# lajta-hfcs.net
KiCad netlist of a schematic drawn in EAGLE
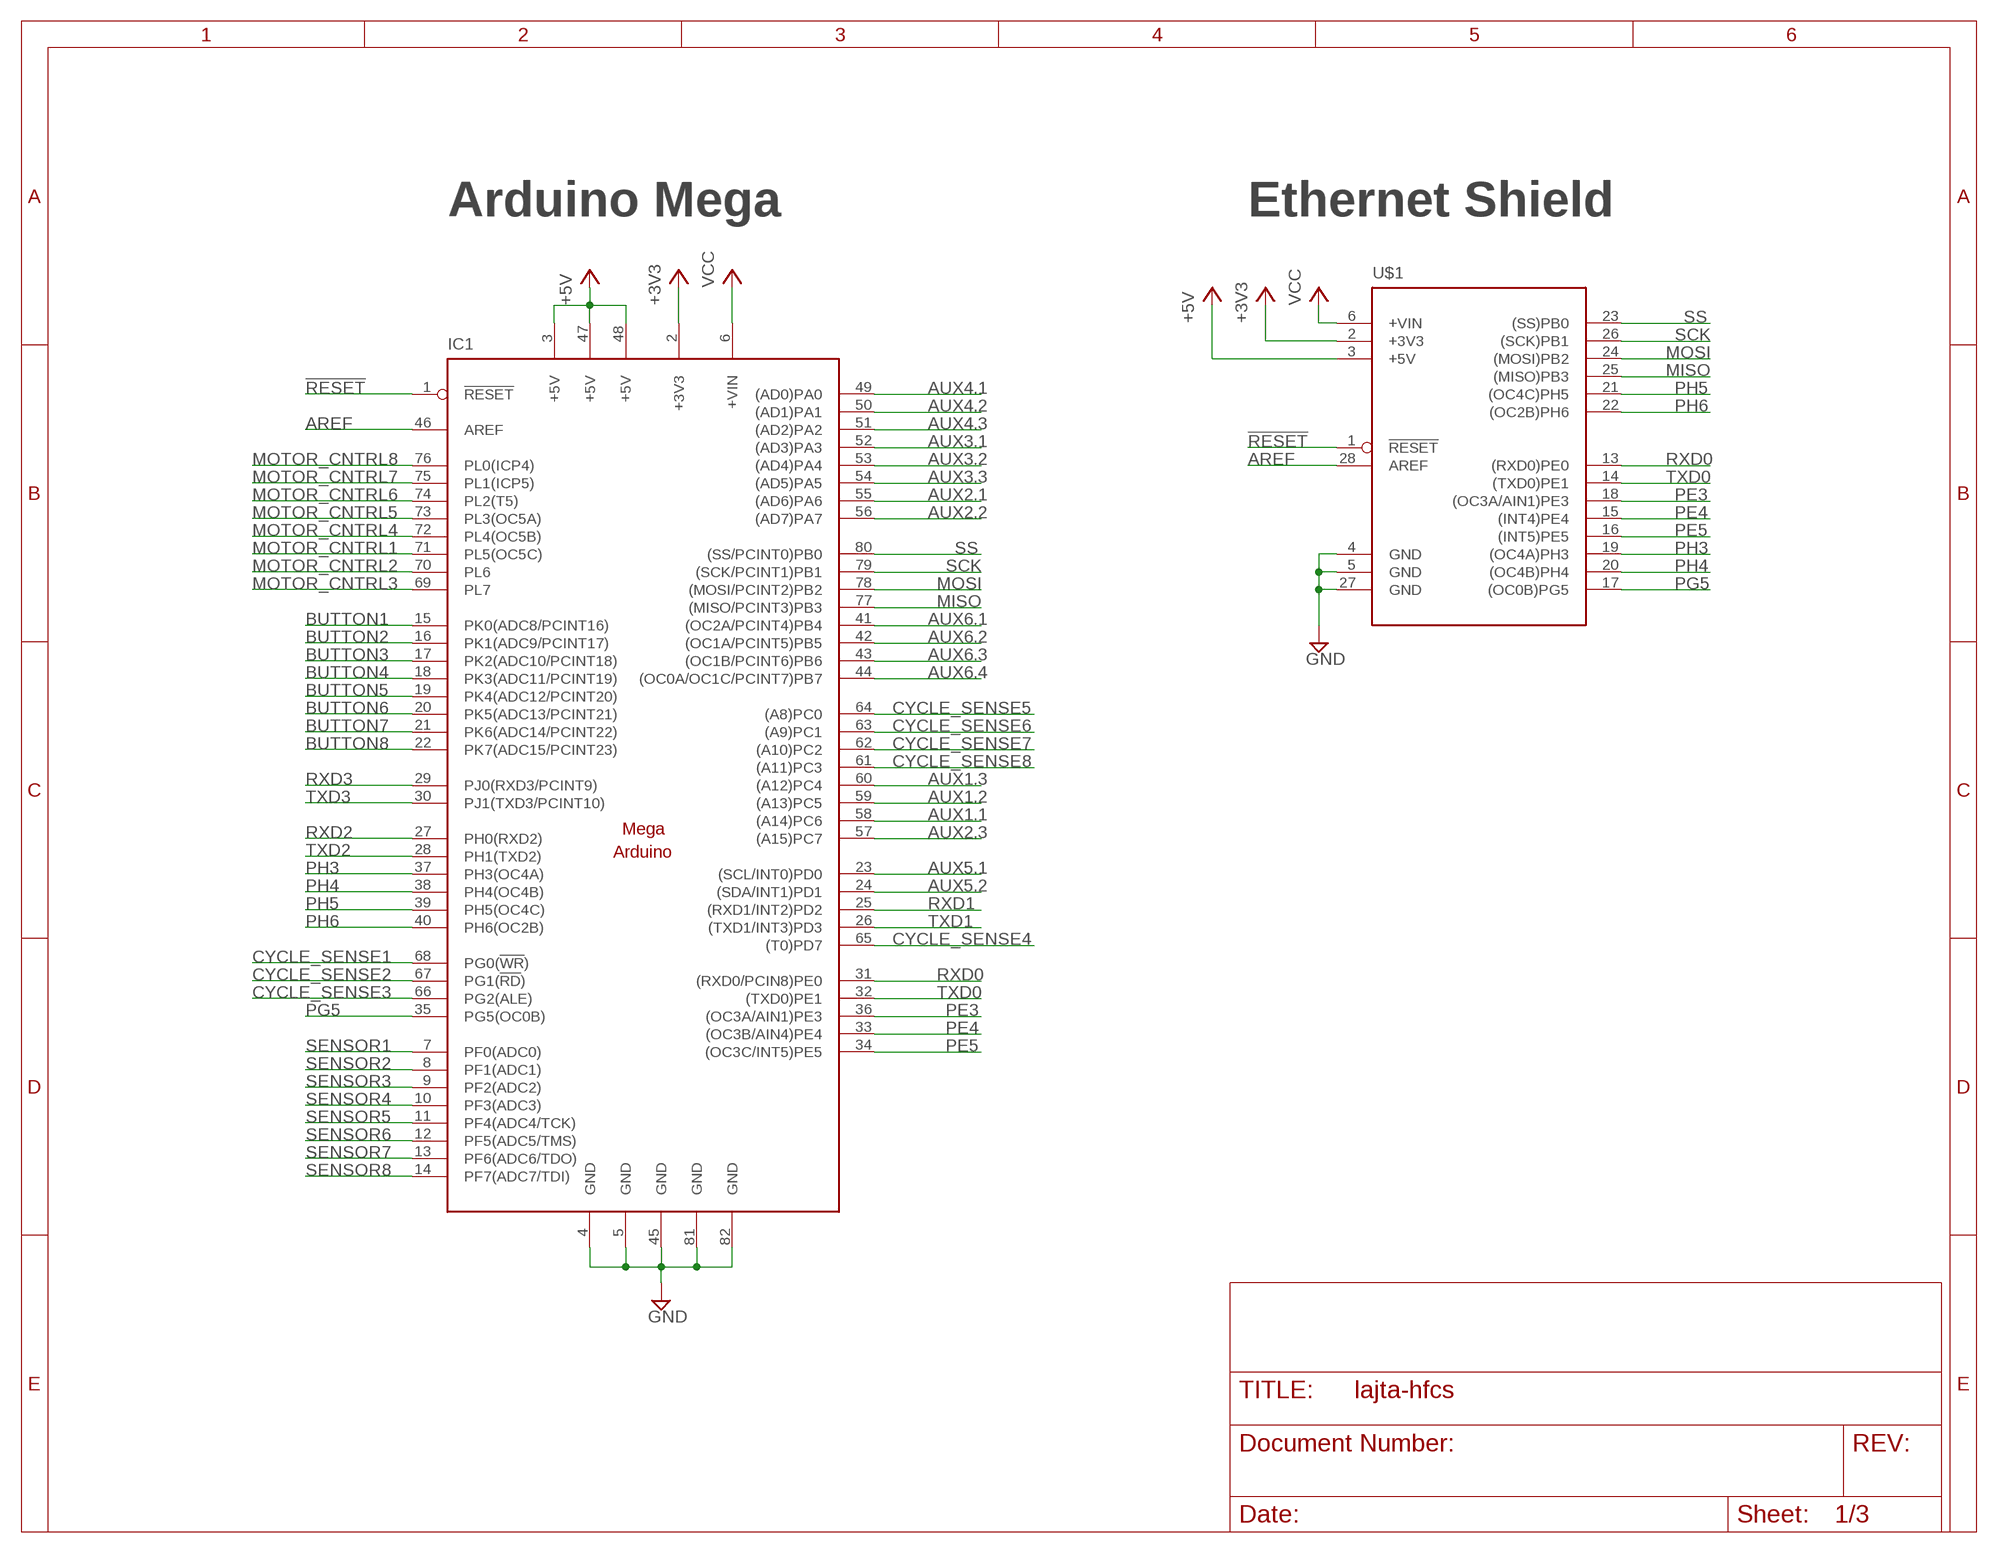
[diagram p0: schematic, sheet 1]
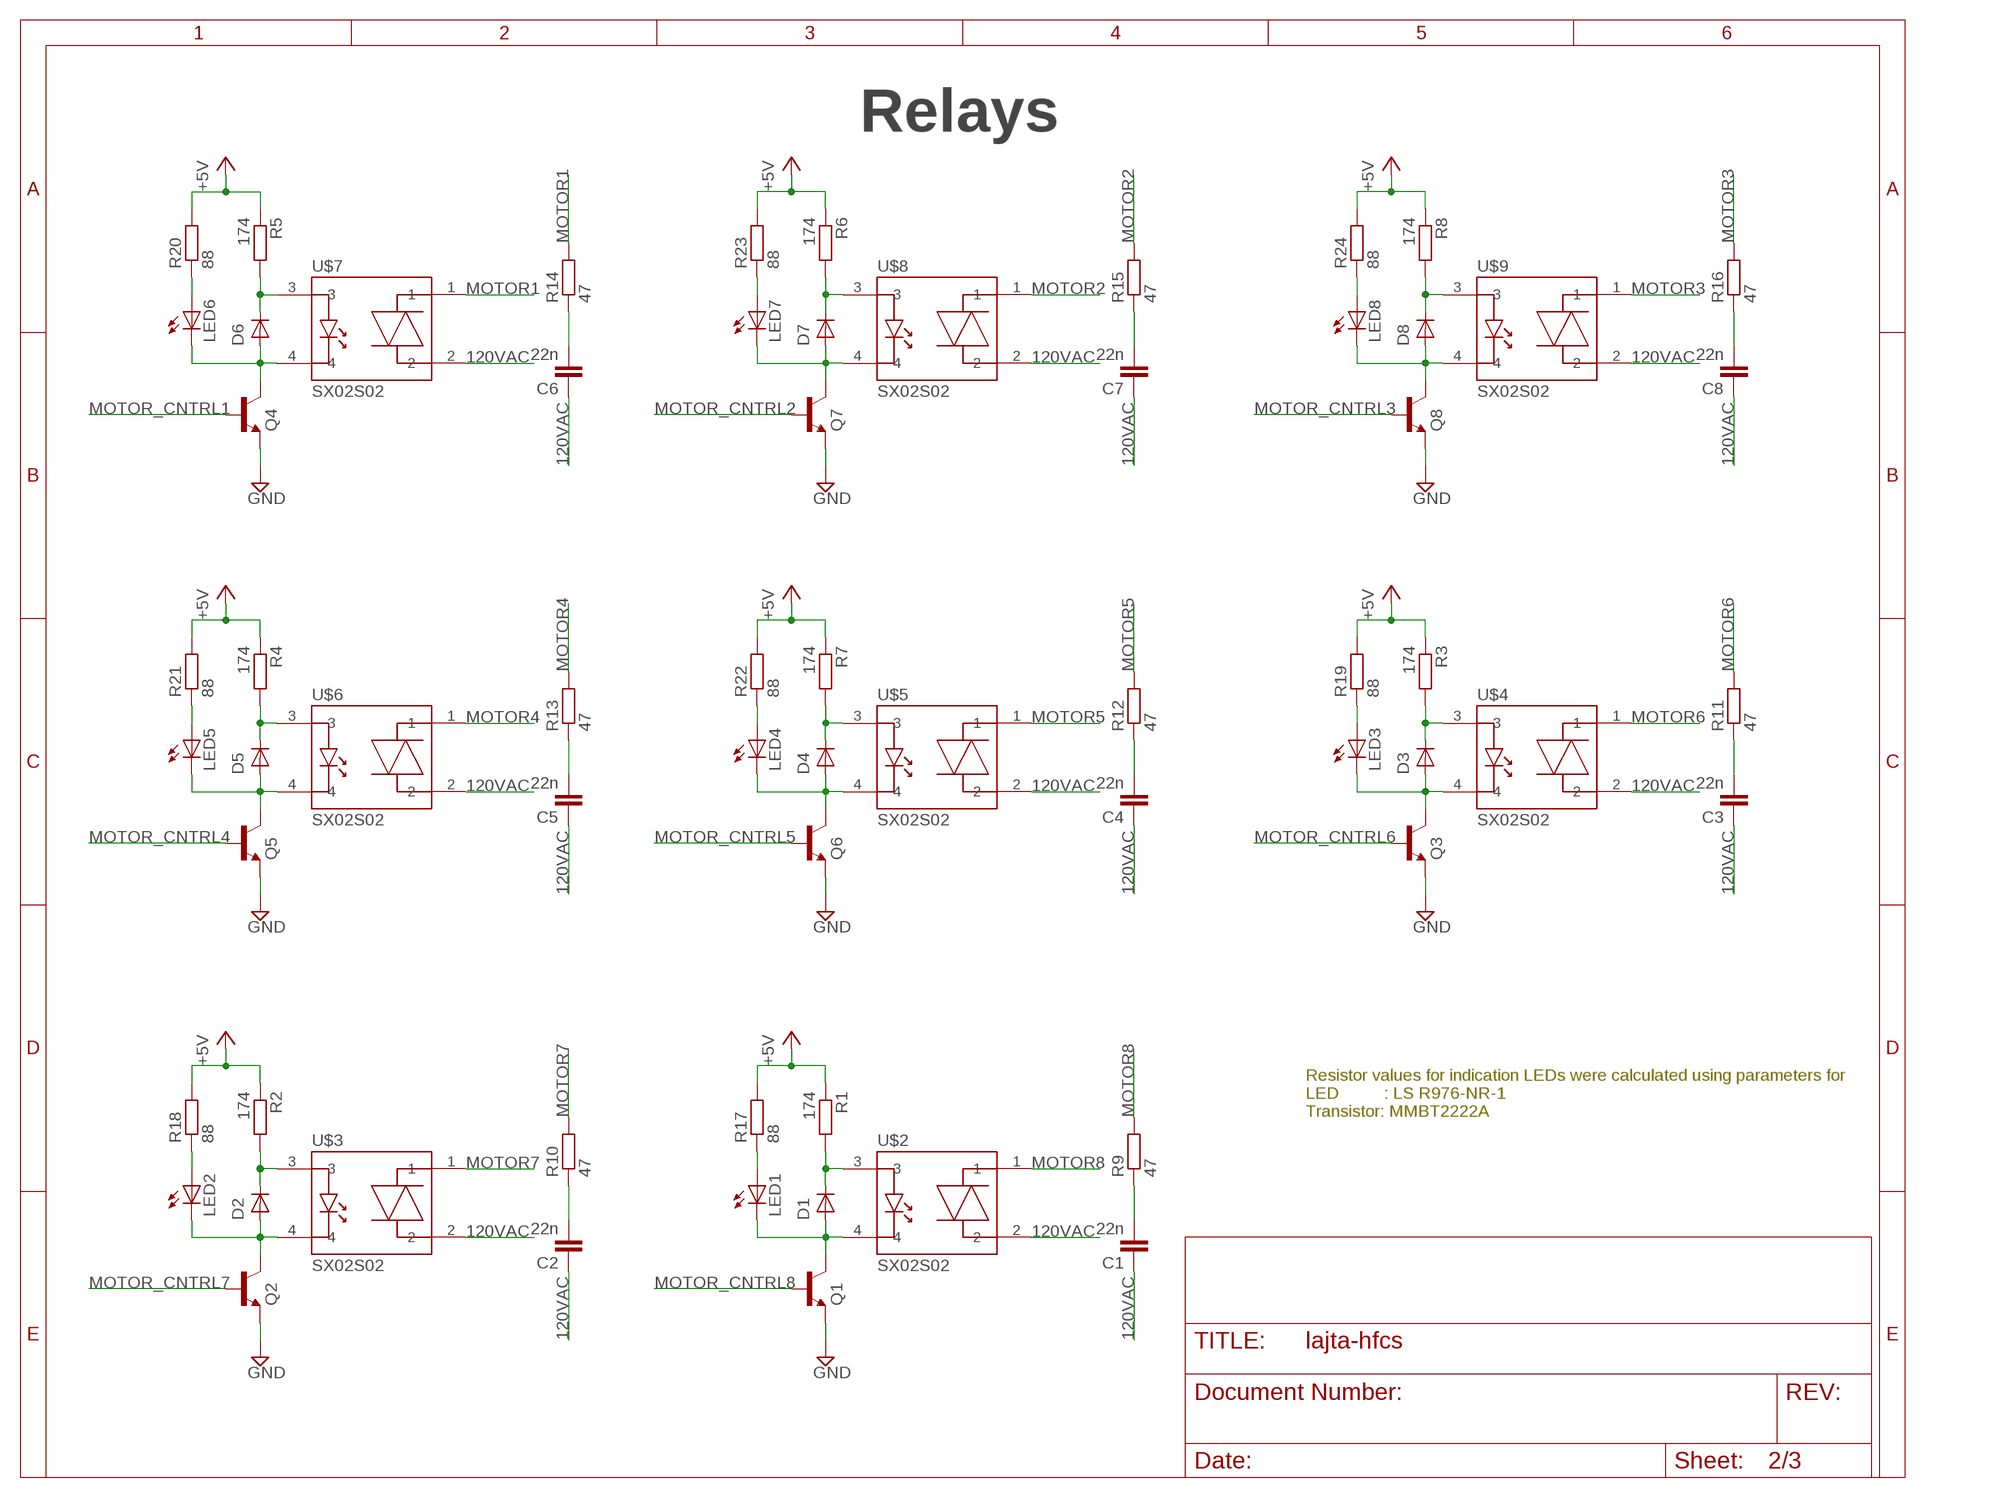
[diagram p1: schematic, sheet 2]
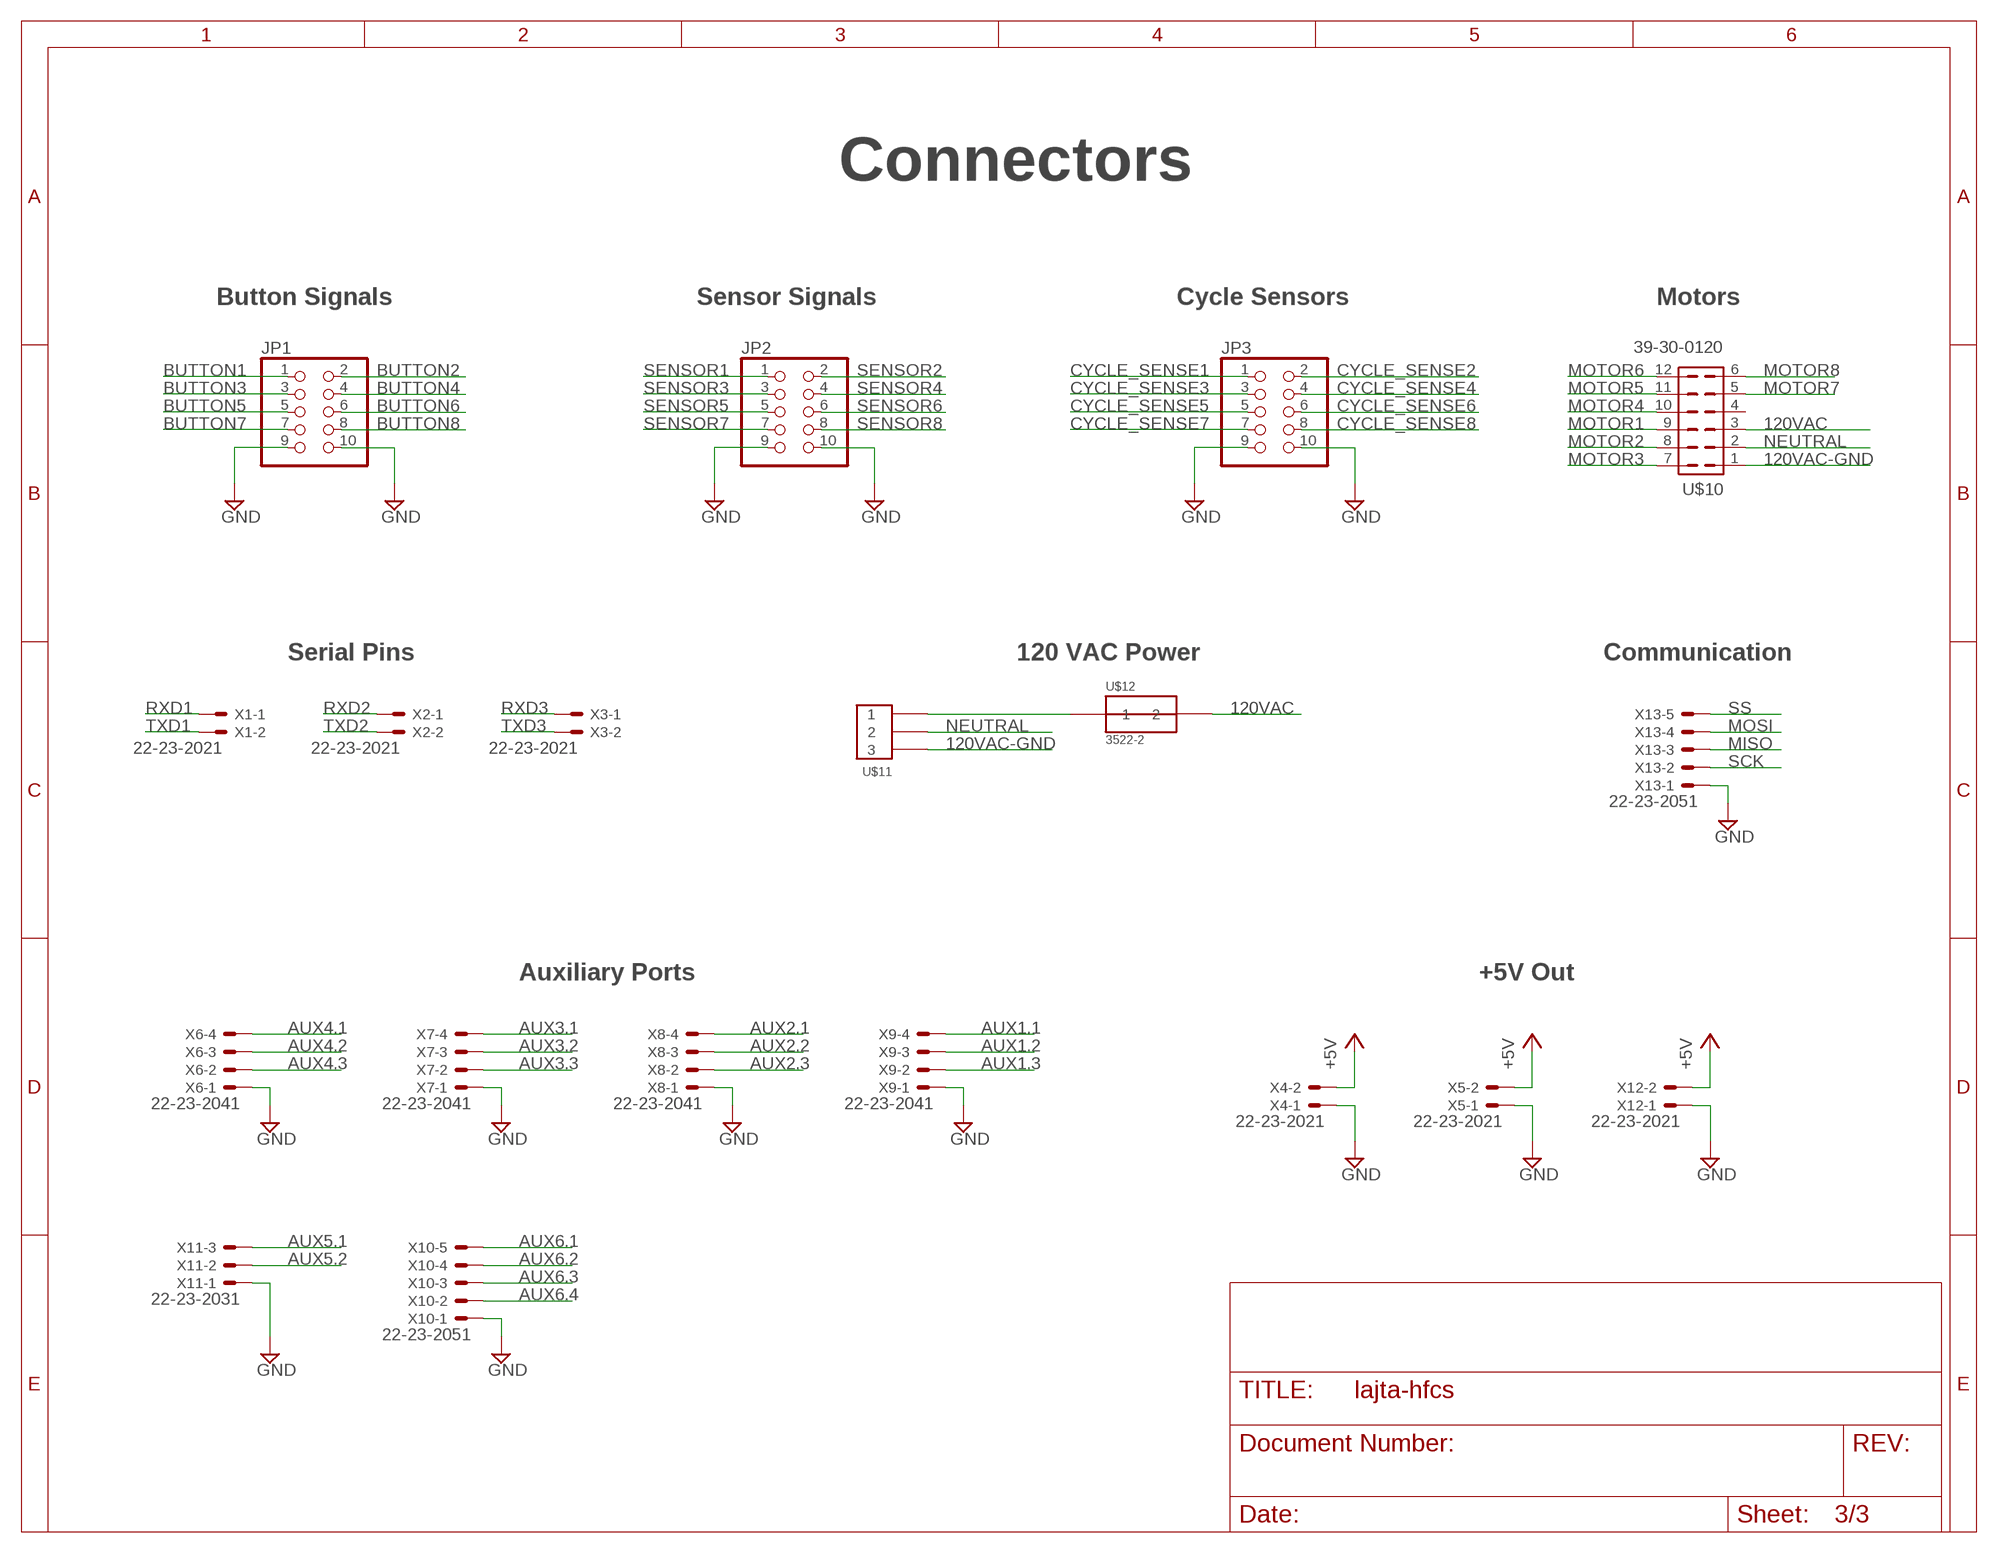
[diagram p2: schematic, sheet 3]

(export (version "E")
  (design (tool "Eeschema 10.0.6"))
  (components
    (comp (ref "JP1")
      (value "PINHD-2X05_2.00")
      (footprint "eagle-import:2X05M")
      (libsource (lib "eagle-import") (part "PINHD-2X05_2.00"))
    )
    (comp (ref "JP2")
      (value "PINHD-2X05_2.00")
      (footprint "eagle-import:2X05M")
      (libsource (lib "eagle-import") (part "PINHD-2X05_2.00"))
    )
    (comp (ref "JP3")
      (value "PINHD-2X05_2.00")
      (footprint "eagle-import:2X05M")
      (libsource (lib "eagle-import") (part "PINHD-2X05_2.00"))
    )
    (comp (ref "U$10")
      (value "39-30-0120")
      (footprint "eagle-import:MINIFIT5569-2-6")
      (libsource (lib "eagle-import") (part "39-30-0120"))
    )
    (comp (ref "U$11")
      (value "39-30-3035")
      (footprint "eagle-import:39-30-3035")
      (libsource (lib "eagle-import") (part "39-30-3035"))
    )
    (comp (ref "U$12")
      (value "3522-2")
      (footprint "eagle-import:ATC")
      (libsource (lib "eagle-import") (part "3522-2"))
    )
    (comp (ref "X1")
      (value "22-23-2021")
      (footprint "eagle-import:22-23-2021")
      (fields (field (name "MF") "MOLEX"))
      (libsource (lib "eagle-import") (part "22-23-2021"))
    )
    (comp (ref "X2")
      (value "22-23-2021")
      (footprint "eagle-import:22-23-2021")
      (fields (field (name "MF") "MOLEX"))
      (libsource (lib "eagle-import") (part "22-23-2021"))
    )
    (comp (ref "X3")
      (value "22-23-2021")
      (footprint "eagle-import:22-23-2021")
      (fields (field (name "MF") "MOLEX"))
      (libsource (lib "eagle-import") (part "22-23-2021"))
    )
    (comp (ref "X4")
      (value "22-23-2021")
      (footprint "eagle-import:22-23-2021")
      (fields (field (name "MF") "MOLEX"))
      (libsource (lib "eagle-import") (part "22-23-2021"))
    )
    (comp (ref "X5")
      (value "22-23-2021")
      (footprint "eagle-import:22-23-2021")
      (fields (field (name "MF") "MOLEX"))
      (libsource (lib "eagle-import") (part "22-23-2021"))
    )
    (comp (ref "X6")
      (value "22-23-2041")
      (footprint "eagle-import:22-23-2041")
      (fields (field (name "MF") "MOLEX"))
      (libsource (lib "eagle-import") (part "22-23-2041"))
    )
    (comp (ref "X7")
      (value "22-23-2041")
      (footprint "eagle-import:22-23-2041")
      (fields (field (name "MF") "MOLEX"))
      (libsource (lib "eagle-import") (part "22-23-2041"))
    )
    (comp (ref "X8")
      (value "22-23-2041")
      (footprint "eagle-import:22-23-2041")
      (fields (field (name "MF") "MOLEX"))
      (libsource (lib "eagle-import") (part "22-23-2041"))
    )
    (comp (ref "X9")
      (value "22-23-2041")
      (footprint "eagle-import:22-23-2041")
      (fields (field (name "MF") "MOLEX"))
      (libsource (lib "eagle-import") (part "22-23-2041"))
    )
    (comp (ref "X10")
      (value "22-23-2051")
      (footprint "eagle-import:22-23-2051")
      (fields (field (name "MF") "MOLEX"))
      (libsource (lib "eagle-import") (part "22-23-2051"))
    )
    (comp (ref "X11")
      (value "22-23-2031")
      (footprint "eagle-import:22-23-2031")
      (fields (field (name "MF") "MOLEX"))
      (libsource (lib "eagle-import") (part "22-23-2031"))
    )
    (comp (ref "X12")
      (value "22-23-2021")
      (footprint "eagle-import:22-23-2021")
      (fields (field (name "MF") "MOLEX"))
      (libsource (lib "eagle-import") (part "22-23-2021"))
    )
    (comp (ref "X13")
      (value "22-23-2051")
      (footprint "eagle-import:22-23-2051")
      (fields (field (name "MF") "MOLEX"))
      (libsource (lib "eagle-import") (part "22-23-2051"))
    )
    (comp (ref "IC1")
      (value "MEGAARDUINO_1")
      (footprint "eagle-import:MEGA_ARDUINO")
      (libsource (lib "eagle-import") (part "MEGAARDUINO_1"))
    )
    (comp (ref "U$1")
      (value "MEGAARDUINO_ETHERNET_SHIELD")
      (footprint "eagle-import:ETHERNET_SHIELD")
      (libsource (lib "eagle-import") (part "MEGAARDUINO_ETHERNET_SHIELD"))
    )
    (comp (ref "C1")
      (value "22n")
      (footprint "eagle-import:C1812")
      (libsource (lib "eagle-import") (part "C-EUC1812"))
    )
    (comp (ref "C2")
      (value "22n")
      (footprint "eagle-import:C1812")
      (libsource (lib "eagle-import") (part "C-EUC1812"))
    )
    (comp (ref "C3")
      (value "22n")
      (footprint "eagle-import:C1812")
      (libsource (lib "eagle-import") (part "C-EUC1812"))
    )
    (comp (ref "C4")
      (value "22n")
      (footprint "eagle-import:C1812")
      (libsource (lib "eagle-import") (part "C-EUC1812"))
    )
    (comp (ref "C5")
      (value "22n")
      (footprint "eagle-import:C1812")
      (libsource (lib "eagle-import") (part "C-EUC1812"))
    )
    (comp (ref "C6")
      (value "22n")
      (footprint "eagle-import:C1812")
      (libsource (lib "eagle-import") (part "C-EUC1812"))
    )
    (comp (ref "C7")
      (value "22n")
      (footprint "eagle-import:C1812")
      (libsource (lib "eagle-import") (part "C-EUC1812"))
    )
    (comp (ref "C8")
      (value "22n")
      (footprint "eagle-import:C1812")
      (libsource (lib "eagle-import") (part "C-EUC1812"))
    )
    (comp (ref "D1")
      (value "1N4448W")
      (footprint "eagle-import:SOD123")
      (libsource (lib "eagle-import") (part "1N4448W"))
    )
    (comp (ref "D2")
      (value "1N4448W")
      (footprint "eagle-import:SOD123")
      (libsource (lib "eagle-import") (part "1N4448W"))
    )
    (comp (ref "D3")
      (value "1N4448W")
      (footprint "eagle-import:SOD123")
      (libsource (lib "eagle-import") (part "1N4448W"))
    )
    (comp (ref "D4")
      (value "1N4448W")
      (footprint "eagle-import:SOD123")
      (libsource (lib "eagle-import") (part "1N4448W"))
    )
    (comp (ref "D5")
      (value "1N4448W")
      (footprint "eagle-import:SOD123")
      (libsource (lib "eagle-import") (part "1N4448W"))
    )
    (comp (ref "D6")
      (value "1N4448W")
      (footprint "eagle-import:SOD123")
      (libsource (lib "eagle-import") (part "1N4448W"))
    )
    (comp (ref "D7")
      (value "1N4448W")
      (footprint "eagle-import:SOD123")
      (libsource (lib "eagle-import") (part "1N4448W"))
    )
    (comp (ref "D8")
      (value "1N4448W")
      (footprint "eagle-import:SOD123")
      (libsource (lib "eagle-import") (part "1N4448W"))
    )
    (comp (ref "LED1")
      (value "LEDCHIPLED_0805")
      (footprint "eagle-import:CHIPLED_0805")
      (libsource (lib "eagle-import") (part "LEDCHIPLED_0805"))
    )
    (comp (ref "LED2")
      (value "LEDCHIPLED_0805")
      (footprint "eagle-import:CHIPLED_0805")
      (libsource (lib "eagle-import") (part "LEDCHIPLED_0805"))
    )
    (comp (ref "LED3")
      (value "LEDCHIPLED_0805")
      (footprint "eagle-import:CHIPLED_0805")
      (libsource (lib "eagle-import") (part "LEDCHIPLED_0805"))
    )
    (comp (ref "LED4")
      (value "LEDCHIPLED_0805")
      (footprint "eagle-import:CHIPLED_0805")
      (libsource (lib "eagle-import") (part "LEDCHIPLED_0805"))
    )
    (comp (ref "LED5")
      (value "LEDCHIPLED_0805")
      (footprint "eagle-import:CHIPLED_0805")
      (libsource (lib "eagle-import") (part "LEDCHIPLED_0805"))
    )
    (comp (ref "LED6")
      (value "LEDCHIPLED_0805")
      (footprint "eagle-import:CHIPLED_0805")
      (libsource (lib "eagle-import") (part "LEDCHIPLED_0805"))
    )
    (comp (ref "LED7")
      (value "LEDCHIPLED_0805")
      (footprint "eagle-import:CHIPLED_0805")
      (libsource (lib "eagle-import") (part "LEDCHIPLED_0805"))
    )
    (comp (ref "LED8")
      (value "LEDCHIPLED_0805")
      (footprint "eagle-import:CHIPLED_0805")
      (libsource (lib "eagle-import") (part "LEDCHIPLED_0805"))
    )
    (comp (ref "Q1")
      (value "MMBT2222A")
      (footprint "eagle-import:SOT23")
      (libsource (lib "eagle-import") (part "MMBT2222A"))
    )
    (comp (ref "Q2")
      (value "MMBT2222A")
      (footprint "eagle-import:SOT23")
      (libsource (lib "eagle-import") (part "MMBT2222A"))
    )
    (comp (ref "Q3")
      (value "MMBT2222A")
      (footprint "eagle-import:SOT23")
      (libsource (lib "eagle-import") (part "MMBT2222A"))
    )
    (comp (ref "Q4")
      (value "MMBT2222A")
      (footprint "eagle-import:SOT23")
      (libsource (lib "eagle-import") (part "MMBT2222A"))
    )
    (comp (ref "Q5")
      (value "MMBT2222A")
      (footprint "eagle-import:SOT23")
      (libsource (lib "eagle-import") (part "MMBT2222A"))
    )
    (comp (ref "Q6")
      (value "MMBT2222A")
      (footprint "eagle-import:SOT23")
      (libsource (lib "eagle-import") (part "MMBT2222A"))
    )
    (comp (ref "Q7")
      (value "MMBT2222A")
      (footprint "eagle-import:SOT23")
      (libsource (lib "eagle-import") (part "MMBT2222A"))
    )
    (comp (ref "Q8")
      (value "MMBT2222A")
      (footprint "eagle-import:SOT23")
      (libsource (lib "eagle-import") (part "MMBT2222A"))
    )
    (comp (ref "R1")
      (value "174")
      (footprint "eagle-import:R0805")
      (libsource (lib "eagle-import") (part "R-EU_R0805"))
    )
    (comp (ref "R2")
      (value "174")
      (footprint "eagle-import:R0805")
      (libsource (lib "eagle-import") (part "R-EU_R0805"))
    )
    (comp (ref "R3")
      (value "174")
      (footprint "eagle-import:R0805")
      (libsource (lib "eagle-import") (part "R-EU_R0805"))
    )
    (comp (ref "R4")
      (value "174")
      (footprint "eagle-import:R0805")
      (libsource (lib "eagle-import") (part "R-EU_R0805"))
    )
    (comp (ref "R5")
      (value "174")
      (footprint "eagle-import:R0805")
      (libsource (lib "eagle-import") (part "R-EU_R0805"))
    )
    (comp (ref "R6")
      (value "174")
      (footprint "eagle-import:R0805")
      (libsource (lib "eagle-import") (part "R-EU_R0805"))
    )
    (comp (ref "R7")
      (value "174")
      (footprint "eagle-import:R0805")
      (libsource (lib "eagle-import") (part "R-EU_R0805"))
    )
    (comp (ref "R8")
      (value "174")
      (footprint "eagle-import:R0805")
      (libsource (lib "eagle-import") (part "R-EU_R0805"))
    )
    (comp (ref "R9")
      (value "47")
      (footprint "eagle-import:R0805")
      (libsource (lib "eagle-import") (part "R-EU_R0805"))
    )
    (comp (ref "R10")
      (value "47")
      (footprint "eagle-import:R0805")
      (libsource (lib "eagle-import") (part "R-EU_R0805"))
    )
    (comp (ref "R11")
      (value "47")
      (footprint "eagle-import:R0805")
      (libsource (lib "eagle-import") (part "R-EU_R0805"))
    )
    (comp (ref "R12")
      (value "47")
      (footprint "eagle-import:R0805")
      (libsource (lib "eagle-import") (part "R-EU_R0805"))
    )
    (comp (ref "R13")
      (value "47")
      (footprint "eagle-import:R0805")
      (libsource (lib "eagle-import") (part "R-EU_R0805"))
    )
    (comp (ref "R14")
      (value "47")
      (footprint "eagle-import:R0805")
      (libsource (lib "eagle-import") (part "R-EU_R0805"))
    )
    (comp (ref "R15")
      (value "47")
      (footprint "eagle-import:R0805")
      (libsource (lib "eagle-import") (part "R-EU_R0805"))
    )
    (comp (ref "R16")
      (value "47")
      (footprint "eagle-import:R0805")
      (libsource (lib "eagle-import") (part "R-EU_R0805"))
    )
    (comp (ref "R17")
      (value "88")
      (footprint "eagle-import:R0805")
      (libsource (lib "eagle-import") (part "R-EU_R0805"))
    )
    (comp (ref "R18")
      (value "88")
      (footprint "eagle-import:R0805")
      (libsource (lib "eagle-import") (part "R-EU_R0805"))
    )
    (comp (ref "R19")
      (value "88")
      (footprint "eagle-import:R0805")
      (libsource (lib "eagle-import") (part "R-EU_R0805"))
    )
    (comp (ref "R20")
      (value "88")
      (footprint "eagle-import:R0805")
      (libsource (lib "eagle-import") (part "R-EU_R0805"))
    )
    (comp (ref "R21")
      (value "88")
      (footprint "eagle-import:R0805")
      (libsource (lib "eagle-import") (part "R-EU_R0805"))
    )
    (comp (ref "R22")
      (value "88")
      (footprint "eagle-import:R0805")
      (libsource (lib "eagle-import") (part "R-EU_R0805"))
    )
    (comp (ref "R23")
      (value "88")
      (footprint "eagle-import:R0805")
      (libsource (lib "eagle-import") (part "R-EU_R0805"))
    )
    (comp (ref "R24")
      (value "88")
      (footprint "eagle-import:R0805")
      (libsource (lib "eagle-import") (part "R-EU_R0805"))
    )
    (comp (ref "U$2")
      (value "SX02S02")
      (footprint "eagle-import:SIP-4")
      (libsource (lib "eagle-import") (part "SX02S02"))
    )
    (comp (ref "U$3")
      (value "SX02S02")
      (footprint "eagle-import:SIP-4")
      (libsource (lib "eagle-import") (part "SX02S02"))
    )
    (comp (ref "U$4")
      (value "SX02S02")
      (footprint "eagle-import:SIP-4")
      (libsource (lib "eagle-import") (part "SX02S02"))
    )
    (comp (ref "U$5")
      (value "SX02S02")
      (footprint "eagle-import:SIP-4")
      (libsource (lib "eagle-import") (part "SX02S02"))
    )
    (comp (ref "U$6")
      (value "SX02S02")
      (footprint "eagle-import:SIP-4")
      (libsource (lib "eagle-import") (part "SX02S02"))
    )
    (comp (ref "U$7")
      (value "SX02S02")
      (footprint "eagle-import:SIP-4")
      (libsource (lib "eagle-import") (part "SX02S02"))
    )
    (comp (ref "U$8")
      (value "SX02S02")
      (footprint "eagle-import:SIP-4")
      (libsource (lib "eagle-import") (part "SX02S02"))
    )
    (comp (ref "U$9")
      (value "SX02S02")
      (footprint "eagle-import:SIP-4")
      (libsource (lib "eagle-import") (part "SX02S02"))
    )
  )
  (nets
    (net (code "1") (name "+3V3") (class "Default")
      (node (ref "IC1") (pin "2") (pinfunction "+3V3_2") (pintype "power_in"))
      (node (ref "U$1") (pin "2") (pinfunction "+3V3_2") (pintype "power_in"))
    )
    (net (code "2") (name "+5V") (class "Default")
      (node (ref "IC1") (pin "3") (pinfunction "+5V_3") (pintype "power_in"))
      (node (ref "IC1") (pin "47") (pinfunction "+5V_47") (pintype "power_in"))
      (node (ref "IC1") (pin "48") (pinfunction "+5V_48") (pintype "power_in"))
      (node (ref "R1") (pin "1") (pinfunction "1_1") (pintype "passive"))
      (node (ref "R17") (pin "2") (pinfunction "2_2") (pintype "passive"))
      (node (ref "R18") (pin "2") (pinfunction "2_2") (pintype "passive"))
      (node (ref "R19") (pin "2") (pinfunction "2_2") (pintype "passive"))
      (node (ref "R2") (pin "1") (pinfunction "1_1") (pintype "passive"))
      (node (ref "R20") (pin "2") (pinfunction "2_2") (pintype "passive"))
      (node (ref "R21") (pin "2") (pinfunction "2_2") (pintype "passive"))
      (node (ref "R22") (pin "2") (pinfunction "2_2") (pintype "passive"))
      (node (ref "R23") (pin "2") (pinfunction "2_2") (pintype "passive"))
      (node (ref "R24") (pin "2") (pinfunction "2_2") (pintype "passive"))
      (node (ref "R3") (pin "1") (pinfunction "1_1") (pintype "passive"))
      (node (ref "R4") (pin "1") (pinfunction "1_1") (pintype "passive"))
      (node (ref "R5") (pin "1") (pinfunction "1_1") (pintype "passive"))
      (node (ref "R6") (pin "1") (pinfunction "1_1") (pintype "passive"))
      (node (ref "R7") (pin "1") (pinfunction "1_1") (pintype "passive"))
      (node (ref "R8") (pin "1") (pinfunction "1_1") (pintype "passive"))
      (node (ref "U$1") (pin "3") (pinfunction "+5V_3") (pintype "power_in"))
      (node (ref "X12") (pin "2") (pinfunction "S_2") (pintype "passive"))
      (node (ref "X4") (pin "2") (pinfunction "S_2") (pintype "passive"))
      (node (ref "X5") (pin "2") (pinfunction "S_2") (pintype "passive"))
    )
    (net (code "3") (name "120VAC") (class "Default")
      (node (ref "C1") (pin "1") (pinfunction "1_1") (pintype "passive"))
      (node (ref "C2") (pin "1") (pinfunction "1_1") (pintype "passive"))
      (node (ref "C3") (pin "1") (pinfunction "1_1") (pintype "passive"))
      (node (ref "C4") (pin "1") (pinfunction "1_1") (pintype "passive"))
      (node (ref "C5") (pin "1") (pinfunction "1_1") (pintype "passive"))
      (node (ref "C6") (pin "1") (pinfunction "1_1") (pintype "passive"))
      (node (ref "C7") (pin "1") (pinfunction "1_1") (pintype "passive"))
      (node (ref "C8") (pin "1") (pinfunction "1_1") (pintype "passive"))
      (node (ref "U$10") (pin "3") (pinfunction "3_3") (pintype "passive"))
      (node (ref "U$12") (pin "4") (pinfunction "2_4") (pintype "bidirectional"))
      (node (ref "U$2") (pin "2") (pinfunction "2_2") (pintype "output"))
      (node (ref "U$3") (pin "2") (pinfunction "2_2") (pintype "output"))
      (node (ref "U$4") (pin "2") (pinfunction "2_2") (pintype "output"))
      (node (ref "U$5") (pin "2") (pinfunction "2_2") (pintype "output"))
      (node (ref "U$6") (pin "2") (pinfunction "2_2") (pintype "output"))
      (node (ref "U$7") (pin "2") (pinfunction "2_2") (pintype "output"))
      (node (ref "U$8") (pin "2") (pinfunction "2_2") (pintype "output"))
      (node (ref "U$9") (pin "2") (pinfunction "2_2") (pintype "output"))
    )
    (net (code "4") (name "120VAC-GND") (class "Default")
      (node (ref "U$10") (pin "1") (pinfunction "1_1") (pintype "passive"))
      (node (ref "U$11") (pin "3") (pinfunction "3_3") (pintype "bidirectional"))
    )
    (net (code "5") (name "AREF") (class "Default")
      (node (ref "IC1") (pin "46") (pinfunction "AREF_46") (pintype "bidirectional"))
      (node (ref "U$1") (pin "28") (pinfunction "AREF_28") (pintype "bidirectional"))
    )
    (net (code "6") (name "AUX1.1") (class "Default")
      (node (ref "IC1") (pin "58") (pinfunction "(A14)PC6_58") (pintype "bidirectional"))
      (node (ref "X9") (pin "4") (pinfunction "S_4") (pintype "passive"))
    )
    (net (code "7") (name "AUX1.2") (class "Default")
      (node (ref "IC1") (pin "59") (pinfunction "(A13)PC5_59") (pintype "bidirectional"))
      (node (ref "X9") (pin "3") (pinfunction "S_3") (pintype "passive"))
    )
    (net (code "8") (name "AUX1.3") (class "Default")
      (node (ref "IC1") (pin "60") (pinfunction "(A12)PC4_60") (pintype "bidirectional"))
      (node (ref "X9") (pin "2") (pinfunction "S_2") (pintype "passive"))
    )
    (net (code "9") (name "AUX2.1") (class "Default")
      (node (ref "IC1") (pin "55") (pinfunction "(AD6)PA6_55") (pintype "bidirectional"))
      (node (ref "X8") (pin "4") (pinfunction "S_4") (pintype "passive"))
    )
    (net (code "10") (name "AUX2.2") (class "Default")
      (node (ref "IC1") (pin "56") (pinfunction "(AD7)PA7_56") (pintype "bidirectional"))
      (node (ref "X8") (pin "3") (pinfunction "S_3") (pintype "passive"))
    )
    (net (code "11") (name "AUX2.3") (class "Default")
      (node (ref "IC1") (pin "57") (pinfunction "(A15)PC7_57") (pintype "bidirectional"))
      (node (ref "X8") (pin "2") (pinfunction "S_2") (pintype "passive"))
    )
    (net (code "12") (name "AUX3.1") (class "Default")
      (node (ref "IC1") (pin "52") (pinfunction "(AD3)PA3_52") (pintype "bidirectional"))
      (node (ref "X7") (pin "4") (pinfunction "S_4") (pintype "passive"))
    )
    (net (code "13") (name "AUX3.2") (class "Default")
      (node (ref "IC1") (pin "53") (pinfunction "(AD4)PA4_53") (pintype "bidirectional"))
      (node (ref "X7") (pin "3") (pinfunction "S_3") (pintype "passive"))
    )
    (net (code "14") (name "AUX3.3") (class "Default")
      (node (ref "IC1") (pin "54") (pinfunction "(AD5)PA5_54") (pintype "bidirectional"))
      (node (ref "X7") (pin "2") (pinfunction "S_2") (pintype "passive"))
    )
    (net (code "15") (name "AUX4.1") (class "Default")
      (node (ref "IC1") (pin "49") (pinfunction "(AD0)PA0_49") (pintype "bidirectional"))
      (node (ref "X6") (pin "4") (pinfunction "S_4") (pintype "passive"))
    )
    (net (code "16") (name "AUX4.2") (class "Default")
      (node (ref "IC1") (pin "50") (pinfunction "(AD1)PA1_50") (pintype "bidirectional"))
      (node (ref "X6") (pin "3") (pinfunction "S_3") (pintype "passive"))
    )
    (net (code "17") (name "AUX4.3") (class "Default")
      (node (ref "IC1") (pin "51") (pinfunction "(AD2)PA2_51") (pintype "bidirectional"))
      (node (ref "X6") (pin "2") (pinfunction "S_2") (pintype "passive"))
    )
    (net (code "18") (name "AUX5.1") (class "Default")
      (node (ref "IC1") (pin "23") (pinfunction "(SCL/INT0)PD0_23") (pintype "bidirectional"))
      (node (ref "X11") (pin "3") (pinfunction "S_3") (pintype "passive"))
    )
    (net (code "19") (name "AUX5.2") (class "Default")
      (node (ref "IC1") (pin "24") (pinfunction "(SDA/INT1)PD1_24") (pintype "bidirectional"))
      (node (ref "X11") (pin "2") (pinfunction "S_2") (pintype "passive"))
    )
    (net (code "20") (name "AUX6.1") (class "Default")
      (node (ref "IC1") (pin "41") (pinfunction "(OC2A/PCINT4)PB4_41") (pintype "bidirectional"))
      (node (ref "X10") (pin "5") (pinfunction "S_5") (pintype "passive"))
    )
    (net (code "21") (name "AUX6.2") (class "Default")
      (node (ref "IC1") (pin "42") (pinfunction "(OC1A/PCINT5)PB5_42") (pintype "bidirectional"))
      (node (ref "X10") (pin "4") (pinfunction "S_4") (pintype "passive"))
    )
    (net (code "22") (name "AUX6.3") (class "Default")
      (node (ref "IC1") (pin "43") (pinfunction "(OC1B/PCINT6)PB6_43") (pintype "bidirectional"))
      (node (ref "X10") (pin "3") (pinfunction "S_3") (pintype "passive"))
    )
    (net (code "23") (name "AUX6.4") (class "Default")
      (node (ref "IC1") (pin "44") (pinfunction "(OC0A/OC1C/PCINT7)PB7_44") (pintype "bidirectional"))
      (node (ref "X10") (pin "2") (pinfunction "S_2") (pintype "passive"))
    )
    (net (code "24") (name "BUTTON1") (class "Default")
      (node (ref "IC1") (pin "15") (pinfunction "PK0(ADC8/PCINT16)_15") (pintype "bidirectional"))
      (node (ref "JP1") (pin "1") (pinfunction "1_1") (pintype "passive"))
    )
    (net (code "25") (name "BUTTON2") (class "Default")
      (node (ref "IC1") (pin "16") (pinfunction "PK1(ADC9/PCINT17)_16") (pintype "bidirectional"))
      (node (ref "JP1") (pin "2") (pinfunction "2_2") (pintype "passive"))
    )
    (net (code "26") (name "BUTTON3") (class "Default")
      (node (ref "IC1") (pin "17") (pinfunction "PK2(ADC10/PCINT18)_17") (pintype "bidirectional"))
      (node (ref "JP1") (pin "3") (pinfunction "3_3") (pintype "passive"))
    )
    (net (code "27") (name "BUTTON4") (class "Default")
      (node (ref "IC1") (pin "18") (pinfunction "PK3(ADC11/PCINT19)_18") (pintype "bidirectional"))
      (node (ref "JP1") (pin "4") (pinfunction "4_4") (pintype "passive"))
    )
    (net (code "28") (name "BUTTON5") (class "Default")
      (node (ref "IC1") (pin "19") (pinfunction "PK4(ADC12/PCINT20)_19") (pintype "bidirectional"))
      (node (ref "JP1") (pin "5") (pinfunction "5_5") (pintype "passive"))
    )
    (net (code "29") (name "BUTTON6") (class "Default")
      (node (ref "IC1") (pin "20") (pinfunction "PK5(ADC13/PCINT21)_20") (pintype "bidirectional"))
      (node (ref "JP1") (pin "6") (pinfunction "6_6") (pintype "passive"))
    )
    (net (code "30") (name "BUTTON7") (class "Default")
      (node (ref "IC1") (pin "21") (pinfunction "PK6(ADC14/PCINT22)_21") (pintype "bidirectional"))
      (node (ref "JP1") (pin "7") (pinfunction "7_7") (pintype "passive"))
    )
    (net (code "31") (name "BUTTON8") (class "Default")
      (node (ref "IC1") (pin "22") (pinfunction "PK7(ADC15/PCINT23)_22") (pintype "bidirectional"))
      (node (ref "JP1") (pin "8") (pinfunction "8_8") (pintype "passive"))
    )
    (net (code "32") (name "CYCLE_SENSE1") (class "Default")
      (node (ref "IC1") (pin "68") (pinfunction "PG0(~{WR})_68") (pintype "bidirectional"))
      (node (ref "JP3") (pin "1") (pinfunction "1_1") (pintype "passive"))
    )
    (net (code "33") (name "CYCLE_SENSE2") (class "Default")
      (node (ref "IC1") (pin "67") (pinfunction "PG1(~{RD})_67") (pintype "bidirectional"))
      (node (ref "JP3") (pin "2") (pinfunction "2_2") (pintype "passive"))
    )
    (net (code "34") (name "CYCLE_SENSE3") (class "Default")
      (node (ref "IC1") (pin "66") (pinfunction "PG2(ALE)_66") (pintype "bidirectional"))
      (node (ref "JP3") (pin "3") (pinfunction "3_3") (pintype "passive"))
    )
    (net (code "35") (name "CYCLE_SENSE4") (class "Default")
      (node (ref "IC1") (pin "65") (pinfunction "(T0)PD7_65") (pintype "bidirectional"))
      (node (ref "JP3") (pin "4") (pinfunction "4_4") (pintype "passive"))
    )
    (net (code "36") (name "CYCLE_SENSE5") (class "Default")
      (node (ref "IC1") (pin "64") (pinfunction "(A8)PC0_64") (pintype "bidirectional"))
      (node (ref "JP3") (pin "5") (pinfunction "5_5") (pintype "passive"))
    )
    (net (code "37") (name "CYCLE_SENSE6") (class "Default")
      (node (ref "IC1") (pin "63") (pinfunction "(A9)PC1_63") (pintype "bidirectional"))
      (node (ref "JP3") (pin "6") (pinfunction "6_6") (pintype "passive"))
    )
    (net (code "38") (name "CYCLE_SENSE7") (class "Default")
      (node (ref "IC1") (pin "62") (pinfunction "(A10)PC2_62") (pintype "bidirectional"))
      (node (ref "JP3") (pin "7") (pinfunction "7_7") (pintype "passive"))
    )
    (net (code "39") (name "CYCLE_SENSE8") (class "Default")
      (node (ref "IC1") (pin "61") (pinfunction "(A11)PC3_61") (pintype "bidirectional"))
      (node (ref "JP3") (pin "8") (pinfunction "8_8") (pintype "passive"))
    )
    (net (code "40") (name "GND") (class "Default")
      (node (ref "IC1") (pin "4") (pinfunction "GND_4") (pintype "power_in"))
      (node (ref "IC1") (pin "45") (pinfunction "GND_45") (pintype "power_in"))
      (node (ref "IC1") (pin "5") (pinfunction "GND_5") (pintype "power_in"))
      (node (ref "IC1") (pin "81") (pinfunction "GND_81") (pintype "power_in"))
      (node (ref "IC1") (pin "82") (pinfunction "GND_82") (pintype "power_in"))
      (node (ref "JP1") (pin "10") (pinfunction "10_10") (pintype "passive"))
      (node (ref "JP1") (pin "9") (pinfunction "9_9") (pintype "passive"))
      (node (ref "JP2") (pin "10") (pinfunction "10_10") (pintype "passive"))
      (node (ref "JP2") (pin "9") (pinfunction "9_9") (pintype "passive"))
      (node (ref "JP3") (pin "10") (pinfunction "10_10") (pintype "passive"))
      (node (ref "JP3") (pin "9") (pinfunction "9_9") (pintype "passive"))
      (node (ref "Q1") (pin "2") (pinfunction "E_2") (pintype "passive"))
      (node (ref "Q2") (pin "2") (pinfunction "E_2") (pintype "passive"))
      (node (ref "Q3") (pin "2") (pinfunction "E_2") (pintype "passive"))
      (node (ref "Q4") (pin "2") (pinfunction "E_2") (pintype "passive"))
      (node (ref "Q5") (pin "2") (pinfunction "E_2") (pintype "passive"))
      (node (ref "Q6") (pin "2") (pinfunction "E_2") (pintype "passive"))
      (node (ref "Q7") (pin "2") (pinfunction "E_2") (pintype "passive"))
      (node (ref "Q8") (pin "2") (pinfunction "E_2") (pintype "passive"))
      (node (ref "U$1") (pin "27") (pinfunction "GND_27") (pintype "power_in"))
      (node (ref "U$1") (pin "4") (pinfunction "GND_4") (pintype "power_in"))
      (node (ref "U$1") (pin "5") (pinfunction "GND_5") (pintype "power_in"))
      (node (ref "X10") (pin "1") (pinfunction "S_1") (pintype "passive"))
      (node (ref "X11") (pin "1") (pinfunction "S_1") (pintype "passive"))
      (node (ref "X12") (pin "1") (pinfunction "S_1") (pintype "passive"))
      (node (ref "X13") (pin "1") (pinfunction "S_1") (pintype "passive"))
      (node (ref "X4") (pin "1") (pinfunction "S_1") (pintype "passive"))
      (node (ref "X5") (pin "1") (pinfunction "S_1") (pintype "passive"))
      (node (ref "X6") (pin "1") (pinfunction "S_1") (pintype "passive"))
      (node (ref "X7") (pin "1") (pinfunction "S_1") (pintype "passive"))
      (node (ref "X8") (pin "1") (pinfunction "S_1") (pintype "passive"))
      (node (ref "X9") (pin "1") (pinfunction "S_1") (pintype "passive"))
    )
    (net (code "41") (name "MISO") (class "Default")
      (node (ref "IC1") (pin "77") (pinfunction "(MISO/PCINT3)PB3_77") (pintype "bidirectional"))
      (node (ref "U$1") (pin "25") (pinfunction "(MISO)PB3_25") (pintype "bidirectional"))
      (node (ref "X13") (pin "3") (pinfunction "S_3") (pintype "passive"))
    )
    (net (code "42") (name "MOSI") (class "Default")
      (node (ref "IC1") (pin "78") (pinfunction "(MOSI/PCINT2)PB2_78") (pintype "bidirectional"))
      (node (ref "U$1") (pin "24") (pinfunction "(MOSI)PB2_24") (pintype "bidirectional"))
      (node (ref "X13") (pin "4") (pinfunction "S_4") (pintype "passive"))
    )
    (net (code "43") (name "MOTOR1") (class "Default")
      (node (ref "R14") (pin "2") (pinfunction "2_2") (pintype "passive"))
      (node (ref "U$10") (pin "9") (pinfunction "9_9") (pintype "passive"))
      (node (ref "U$7") (pin "1") (pinfunction "1_1") (pintype "output"))
    )
    (net (code "44") (name "MOTOR2") (class "Default")
      (node (ref "R15") (pin "2") (pinfunction "2_2") (pintype "passive"))
      (node (ref "U$10") (pin "8") (pinfunction "8_8") (pintype "passive"))
      (node (ref "U$8") (pin "1") (pinfunction "1_1") (pintype "output"))
    )
    (net (code "45") (name "MOTOR3") (class "Default")
      (node (ref "R16") (pin "2") (pinfunction "2_2") (pintype "passive"))
      (node (ref "U$10") (pin "7") (pinfunction "7_7") (pintype "passive"))
      (node (ref "U$9") (pin "1") (pinfunction "1_1") (pintype "output"))
    )
    (net (code "46") (name "MOTOR4") (class "Default")
      (node (ref "R13") (pin "2") (pinfunction "2_2") (pintype "passive"))
      (node (ref "U$10") (pin "10") (pinfunction "10_10") (pintype "passive"))
      (node (ref "U$6") (pin "1") (pinfunction "1_1") (pintype "output"))
    )
    (net (code "47") (name "MOTOR5") (class "Default")
      (node (ref "R12") (pin "2") (pinfunction "2_2") (pintype "passive"))
      (node (ref "U$10") (pin "11") (pinfunction "11_11") (pintype "passive"))
      (node (ref "U$5") (pin "1") (pinfunction "1_1") (pintype "output"))
    )
    (net (code "48") (name "MOTOR6") (class "Default")
      (node (ref "R11") (pin "2") (pinfunction "2_2") (pintype "passive"))
      (node (ref "U$10") (pin "12") (pinfunction "12_12") (pintype "passive"))
      (node (ref "U$4") (pin "1") (pinfunction "1_1") (pintype "output"))
    )
    (net (code "49") (name "MOTOR7") (class "Default")
      (node (ref "R10") (pin "2") (pinfunction "2_2") (pintype "passive"))
      (node (ref "U$10") (pin "5") (pinfunction "5_5") (pintype "passive"))
      (node (ref "U$3") (pin "1") (pinfunction "1_1") (pintype "output"))
    )
    (net (code "50") (name "MOTOR8") (class "Default")
      (node (ref "R9") (pin "2") (pinfunction "2_2") (pintype "passive"))
      (node (ref "U$10") (pin "6") (pinfunction "6_6") (pintype "passive"))
      (node (ref "U$2") (pin "1") (pinfunction "1_1") (pintype "output"))
    )
    (net (code "51") (name "MOTOR_CNTRL1") (class "Default")
      (node (ref "IC1") (pin "71") (pinfunction "PL5(OC5C)_71") (pintype "bidirectional"))
      (node (ref "Q4") (pin "1") (pinfunction "B_1") (pintype "passive"))
    )
    (net (code "52") (name "MOTOR_CNTRL2") (class "Default")
      (node (ref "IC1") (pin "70") (pinfunction "PL6_70") (pintype "bidirectional"))
      (node (ref "Q7") (pin "1") (pinfunction "B_1") (pintype "passive"))
    )
    (net (code "53") (name "MOTOR_CNTRL3") (class "Default")
      (node (ref "IC1") (pin "69") (pinfunction "PL7_69") (pintype "bidirectional"))
      (node (ref "Q8") (pin "1") (pinfunction "B_1") (pintype "passive"))
    )
    (net (code "54") (name "MOTOR_CNTRL4") (class "Default")
      (node (ref "IC1") (pin "72") (pinfunction "PL4(OC5B)_72") (pintype "bidirectional"))
      (node (ref "Q5") (pin "1") (pinfunction "B_1") (pintype "passive"))
    )
    (net (code "55") (name "MOTOR_CNTRL5") (class "Default")
      (node (ref "IC1") (pin "73") (pinfunction "PL3(OC5A)_73") (pintype "bidirectional"))
      (node (ref "Q6") (pin "1") (pinfunction "B_1") (pintype "passive"))
    )
    (net (code "56") (name "MOTOR_CNTRL6") (class "Default")
      (node (ref "IC1") (pin "74") (pinfunction "PL2(T5)_74") (pintype "bidirectional"))
      (node (ref "Q3") (pin "1") (pinfunction "B_1") (pintype "passive"))
    )
    (net (code "57") (name "MOTOR_CNTRL7") (class "Default")
      (node (ref "IC1") (pin "75") (pinfunction "PL1(ICP5)_75") (pintype "bidirectional"))
      (node (ref "Q2") (pin "1") (pinfunction "B_1") (pintype "passive"))
    )
    (net (code "58") (name "MOTOR_CNTRL8") (class "Default")
      (node (ref "IC1") (pin "76") (pinfunction "PL0(ICP4)_76") (pintype "bidirectional"))
      (node (ref "Q1") (pin "1") (pinfunction "B_1") (pintype "passive"))
    )
    (net (code "59") (name "NEUTRAL") (class "Default")
      (node (ref "U$10") (pin "2") (pinfunction "2_2") (pintype "passive"))
      (node (ref "U$11") (pin "2") (pinfunction "2_2") (pintype "bidirectional"))
    )
    (net (code "60") (name "Net-(C1-Pad2)") (class "Default")
      (node (ref "C1") (pin "2") (pinfunction "2_2") (pintype "passive"))
      (node (ref "R9") (pin "1") (pinfunction "1_1") (pintype "passive"))
    )
    (net (code "61") (name "Net-(C2-Pad2)") (class "Default")
      (node (ref "C2") (pin "2") (pinfunction "2_2") (pintype "passive"))
      (node (ref "R10") (pin "1") (pinfunction "1_1") (pintype "passive"))
    )
    (net (code "62") (name "Net-(C3-Pad2)") (class "Default")
      (node (ref "C3") (pin "2") (pinfunction "2_2") (pintype "passive"))
      (node (ref "R11") (pin "1") (pinfunction "1_1") (pintype "passive"))
    )
    (net (code "63") (name "Net-(C4-Pad2)") (class "Default")
      (node (ref "C4") (pin "2") (pinfunction "2_2") (pintype "passive"))
      (node (ref "R12") (pin "1") (pinfunction "1_1") (pintype "passive"))
    )
    (net (code "64") (name "Net-(C5-Pad2)") (class "Default")
      (node (ref "C5") (pin "2") (pinfunction "2_2") (pintype "passive"))
      (node (ref "R13") (pin "1") (pinfunction "1_1") (pintype "passive"))
    )
    (net (code "65") (name "Net-(C6-Pad2)") (class "Default")
      (node (ref "C6") (pin "2") (pinfunction "2_2") (pintype "passive"))
      (node (ref "R14") (pin "1") (pinfunction "1_1") (pintype "passive"))
    )
    (net (code "66") (name "Net-(C7-Pad2)") (class "Default")
      (node (ref "C7") (pin "2") (pinfunction "2_2") (pintype "passive"))
      (node (ref "R15") (pin "1") (pinfunction "1_1") (pintype "passive"))
    )
    (net (code "67") (name "Net-(C8-Pad2)") (class "Default")
      (node (ref "C8") (pin "2") (pinfunction "2_2") (pintype "passive"))
      (node (ref "R16") (pin "1") (pinfunction "1_1") (pintype "passive"))
    )
    (net (code "68") (name "Net-(D1-PadC)") (class "Default")
      (node (ref "D1") (pin "C") (pinfunction "C_C") (pintype "passive"))
      (node (ref "R1") (pin "2") (pinfunction "2_2") (pintype "passive"))
      (node (ref "U$2") (pin "3") (pinfunction "3_3") (pintype "input"))
    )
    (net (code "69") (name "Net-(D2-PadC)") (class "Default")
      (node (ref "D2") (pin "C") (pinfunction "C_C") (pintype "passive"))
      (node (ref "R2") (pin "2") (pinfunction "2_2") (pintype "passive"))
      (node (ref "U$3") (pin "3") (pinfunction "3_3") (pintype "input"))
    )
    (net (code "70") (name "Net-(D3-PadC)") (class "Default")
      (node (ref "D3") (pin "C") (pinfunction "C_C") (pintype "passive"))
      (node (ref "R3") (pin "2") (pinfunction "2_2") (pintype "passive"))
      (node (ref "U$4") (pin "3") (pinfunction "3_3") (pintype "input"))
    )
    (net (code "71") (name "Net-(D4-PadC)") (class "Default")
      (node (ref "D4") (pin "C") (pinfunction "C_C") (pintype "passive"))
      (node (ref "R7") (pin "2") (pinfunction "2_2") (pintype "passive"))
      (node (ref "U$5") (pin "3") (pinfunction "3_3") (pintype "input"))
    )
    (net (code "72") (name "Net-(D5-PadC)") (class "Default")
      (node (ref "D5") (pin "C") (pinfunction "C_C") (pintype "passive"))
      (node (ref "R4") (pin "2") (pinfunction "2_2") (pintype "passive"))
      (node (ref "U$6") (pin "3") (pinfunction "3_3") (pintype "input"))
    )
    (net (code "73") (name "Net-(D6-PadC)") (class "Default")
      (node (ref "D6") (pin "C") (pinfunction "C_C") (pintype "passive"))
      (node (ref "R5") (pin "2") (pinfunction "2_2") (pintype "passive"))
      (node (ref "U$7") (pin "3") (pinfunction "3_3") (pintype "input"))
    )
    (net (code "74") (name "Net-(D7-PadC)") (class "Default")
      (node (ref "D7") (pin "C") (pinfunction "C_C") (pintype "passive"))
      (node (ref "R6") (pin "2") (pinfunction "2_2") (pintype "passive"))
      (node (ref "U$8") (pin "3") (pinfunction "3_3") (pintype "input"))
    )
    (net (code "75") (name "Net-(D8-PadC)") (class "Default")
      (node (ref "D8") (pin "C") (pinfunction "C_C") (pintype "passive"))
      (node (ref "R8") (pin "2") (pinfunction "2_2") (pintype "passive"))
      (node (ref "U$9") (pin "3") (pinfunction "3_3") (pintype "input"))
    )
    (net (code "76") (name "Net-(LED1-PadA)") (class "Default")
      (node (ref "LED1") (pin "A") (pinfunction "A_A") (pintype "passive"))
      (node (ref "R17") (pin "1") (pinfunction "1_1") (pintype "passive"))
    )
    (net (code "77") (name "Net-(LED2-PadA)") (class "Default")
      (node (ref "LED2") (pin "A") (pinfunction "A_A") (pintype "passive"))
      (node (ref "R18") (pin "1") (pinfunction "1_1") (pintype "passive"))
    )
    (net (code "78") (name "Net-(LED3-PadA)") (class "Default")
      (node (ref "LED3") (pin "A") (pinfunction "A_A") (pintype "passive"))
      (node (ref "R19") (pin "1") (pinfunction "1_1") (pintype "passive"))
    )
    (net (code "79") (name "Net-(LED4-PadA)") (class "Default")
      (node (ref "LED4") (pin "A") (pinfunction "A_A") (pintype "passive"))
      (node (ref "R22") (pin "1") (pinfunction "1_1") (pintype "passive"))
    )
    (net (code "80") (name "Net-(LED5-PadA)") (class "Default")
      (node (ref "LED5") (pin "A") (pinfunction "A_A") (pintype "passive"))
      (node (ref "R21") (pin "1") (pinfunction "1_1") (pintype "passive"))
    )
    (net (code "81") (name "Net-(LED6-PadA)") (class "Default")
      (node (ref "LED6") (pin "A") (pinfunction "A_A") (pintype "passive"))
      (node (ref "R20") (pin "1") (pinfunction "1_1") (pintype "passive"))
    )
    (net (code "82") (name "Net-(LED7-PadA)") (class "Default")
      (node (ref "LED7") (pin "A") (pinfunction "A_A") (pintype "passive"))
      (node (ref "R23") (pin "1") (pinfunction "1_1") (pintype "passive"))
    )
    (net (code "83") (name "Net-(LED8-PadA)") (class "Default")
      (node (ref "LED8") (pin "A") (pinfunction "A_A") (pintype "passive"))
      (node (ref "R24") (pin "1") (pinfunction "1_1") (pintype "passive"))
    )
    (net (code "84") (name "Net-(Q1-C)") (class "Default")
      (node (ref "D1") (pin "A") (pinfunction "A_A") (pintype "passive"))
      (node (ref "LED1") (pin "C") (pinfunction "C_C") (pintype "passive"))
      (node (ref "Q1") (pin "3") (pinfunction "C_3") (pintype "passive"))
      (node (ref "U$2") (pin "4") (pinfunction "4_4") (pintype "input"))
    )
    (net (code "85") (name "Net-(Q2-C)") (class "Default")
      (node (ref "D2") (pin "A") (pinfunction "A_A") (pintype "passive"))
      (node (ref "LED2") (pin "C") (pinfunction "C_C") (pintype "passive"))
      (node (ref "Q2") (pin "3") (pinfunction "C_3") (pintype "passive"))
      (node (ref "U$3") (pin "4") (pinfunction "4_4") (pintype "input"))
    )
    (net (code "86") (name "Net-(Q3-C)") (class "Default")
      (node (ref "D3") (pin "A") (pinfunction "A_A") (pintype "passive"))
      (node (ref "LED3") (pin "C") (pinfunction "C_C") (pintype "passive"))
      (node (ref "Q3") (pin "3") (pinfunction "C_3") (pintype "passive"))
      (node (ref "U$4") (pin "4") (pinfunction "4_4") (pintype "input"))
    )
    (net (code "87") (name "Net-(Q4-C)") (class "Default")
      (node (ref "D6") (pin "A") (pinfunction "A_A") (pintype "passive"))
      (node (ref "LED6") (pin "C") (pinfunction "C_C") (pintype "passive"))
      (node (ref "Q4") (pin "3") (pinfunction "C_3") (pintype "passive"))
      (node (ref "U$7") (pin "4") (pinfunction "4_4") (pintype "input"))
    )
    (net (code "88") (name "Net-(Q5-C)") (class "Default")
      (node (ref "D5") (pin "A") (pinfunction "A_A") (pintype "passive"))
      (node (ref "LED5") (pin "C") (pinfunction "C_C") (pintype "passive"))
      (node (ref "Q5") (pin "3") (pinfunction "C_3") (pintype "passive"))
      (node (ref "U$6") (pin "4") (pinfunction "4_4") (pintype "input"))
    )
    (net (code "89") (name "Net-(Q6-C)") (class "Default")
      (node (ref "D4") (pin "A") (pinfunction "A_A") (pintype "passive"))
      (node (ref "LED4") (pin "C") (pinfunction "C_C") (pintype "passive"))
      (node (ref "Q6") (pin "3") (pinfunction "C_3") (pintype "passive"))
      (node (ref "U$5") (pin "4") (pinfunction "4_4") (pintype "input"))
    )
    (net (code "90") (name "Net-(Q7-C)") (class "Default")
      (node (ref "D7") (pin "A") (pinfunction "A_A") (pintype "passive"))
      (node (ref "LED7") (pin "C") (pinfunction "C_C") (pintype "passive"))
      (node (ref "Q7") (pin "3") (pinfunction "C_3") (pintype "passive"))
      (node (ref "U$8") (pin "4") (pinfunction "4_4") (pintype "input"))
    )
    (net (code "91") (name "Net-(Q8-C)") (class "Default")
      (node (ref "D8") (pin "A") (pinfunction "A_A") (pintype "passive"))
      (node (ref "LED8") (pin "C") (pinfunction "C_C") (pintype "passive"))
      (node (ref "Q8") (pin "3") (pinfunction "C_3") (pintype "passive"))
      (node (ref "U$9") (pin "4") (pinfunction "4_4") (pintype "input"))
    )
    (net (code "92") (name "Net-(U$11-Pad1)") (class "Default")
      (node (ref "U$11") (pin "1") (pinfunction "1_1") (pintype "bidirectional"))
      (node (ref "U$12") (pin "1") (pinfunction "1_1") (pintype "bidirectional"))
    )
    (net (code "93") (name "PE3") (class "Default")
      (node (ref "IC1") (pin "36") (pinfunction "(OC3A/AIN1)PE3_36") (pintype "bidirectional"))
      (node (ref "U$1") (pin "18") (pinfunction "(OC3A/AIN1)PE3_18") (pintype "bidirectional"))
    )
    (net (code "94") (name "PE4") (class "Default")
      (node (ref "IC1") (pin "33") (pinfunction "(OC3B/AIN4)PE4_33") (pintype "bidirectional"))
      (node (ref "U$1") (pin "15") (pinfunction "(INT4)PE4_15") (pintype "bidirectional"))
    )
    (net (code "95") (name "PE5") (class "Default")
      (node (ref "IC1") (pin "34") (pinfunction "(OC3C/INT5)PE5_34") (pintype "bidirectional"))
      (node (ref "U$1") (pin "16") (pinfunction "(INT5)PE5_16") (pintype "bidirectional"))
    )
    (net (code "96") (name "PG5") (class "Default")
      (node (ref "IC1") (pin "35") (pinfunction "PG5(OC0B)_35") (pintype "bidirectional"))
      (node (ref "U$1") (pin "17") (pinfunction "(OC0B)PG5_17") (pintype "bidirectional"))
    )
    (net (code "97") (name "PH3") (class "Default")
      (node (ref "IC1") (pin "37") (pinfunction "PH3(OC4A)_37") (pintype "bidirectional"))
      (node (ref "U$1") (pin "19") (pinfunction "(OC4A)PH3_19") (pintype "bidirectional"))
    )
    (net (code "98") (name "PH4") (class "Default")
      (node (ref "IC1") (pin "38") (pinfunction "PH4(OC4B)_38") (pintype "bidirectional"))
      (node (ref "U$1") (pin "20") (pinfunction "(OC4B)PH4_20") (pintype "bidirectional"))
    )
    (net (code "99") (name "PH5") (class "Default")
      (node (ref "IC1") (pin "39") (pinfunction "PH5(OC4C)_39") (pintype "bidirectional"))
      (node (ref "U$1") (pin "21") (pinfunction "(OC4C)PH5_21") (pintype "bidirectional"))
    )
    (net (code "100") (name "PH6") (class "Default")
      (node (ref "IC1") (pin "40") (pinfunction "PH6(OC2B)_40") (pintype "bidirectional"))
      (node (ref "U$1") (pin "22") (pinfunction "(OC2B)PH6_22") (pintype "bidirectional"))
    )
    (net (code "101") (name "RXD0") (class "Default")
      (node (ref "IC1") (pin "31") (pinfunction "(RXD0/PCIN8)PE0_31") (pintype "bidirectional"))
      (node (ref "U$1") (pin "13") (pinfunction "(RXD0)PE0_13") (pintype "bidirectional"))
    )
    (net (code "102") (name "RXD1") (class "Default")
      (node (ref "IC1") (pin "25") (pinfunction "(RXD1/INT2)PD2_25") (pintype "bidirectional"))
      (node (ref "X1") (pin "1") (pinfunction "S_1") (pintype "passive"))
    )
    (net (code "103") (name "RXD2") (class "Default")
      (node (ref "IC1") (pin "27") (pinfunction "PH0(RXD2)_27") (pintype "bidirectional"))
      (node (ref "X2") (pin "1") (pinfunction "S_1") (pintype "passive"))
    )
    (net (code "104") (name "RXD3") (class "Default")
      (node (ref "IC1") (pin "29") (pinfunction "PJ0(RXD3/PCINT9)_29") (pintype "bidirectional"))
      (node (ref "X3") (pin "1") (pinfunction "S_1") (pintype "passive"))
    )
    (net (code "105") (name "SCK") (class "Default")
      (node (ref "IC1") (pin "79") (pinfunction "(SCK/PCINT1)PB1_79") (pintype "bidirectional"))
      (node (ref "U$1") (pin "26") (pinfunction "(SCK)PB1_26") (pintype "bidirectional"))
      (node (ref "X13") (pin "2") (pinfunction "S_2") (pintype "passive"))
    )
    (net (code "106") (name "SENSOR1") (class "Default")
      (node (ref "IC1") (pin "7") (pinfunction "PF0(ADC0)_7") (pintype "bidirectional"))
      (node (ref "JP2") (pin "1") (pinfunction "1_1") (pintype "passive"))
    )
    (net (code "107") (name "SENSOR2") (class "Default")
      (node (ref "IC1") (pin "8") (pinfunction "PF1(ADC1)_8") (pintype "bidirectional"))
      (node (ref "JP2") (pin "2") (pinfunction "2_2") (pintype "passive"))
    )
    (net (code "108") (name "SENSOR3") (class "Default")
      (node (ref "IC1") (pin "9") (pinfunction "PF2(ADC2)_9") (pintype "bidirectional"))
      (node (ref "JP2") (pin "3") (pinfunction "3_3") (pintype "passive"))
    )
    (net (code "109") (name "SENSOR4") (class "Default")
      (node (ref "IC1") (pin "10") (pinfunction "PF3(ADC3)_10") (pintype "bidirectional"))
      (node (ref "JP2") (pin "4") (pinfunction "4_4") (pintype "passive"))
    )
    (net (code "110") (name "SENSOR5") (class "Default")
      (node (ref "IC1") (pin "11") (pinfunction "PF4(ADC4/TCK)_11") (pintype "bidirectional"))
      (node (ref "JP2") (pin "5") (pinfunction "5_5") (pintype "passive"))
    )
    (net (code "111") (name "SENSOR6") (class "Default")
      (node (ref "IC1") (pin "12") (pinfunction "PF5(ADC5/TMS)_12") (pintype "bidirectional"))
      (node (ref "JP2") (pin "6") (pinfunction "6_6") (pintype "passive"))
    )
    (net (code "112") (name "SENSOR7") (class "Default")
      (node (ref "IC1") (pin "13") (pinfunction "PF6(ADC6/TDO)_13") (pintype "bidirectional"))
      (node (ref "JP2") (pin "7") (pinfunction "7_7") (pintype "passive"))
    )
    (net (code "113") (name "SENSOR8") (class "Default")
      (node (ref "IC1") (pin "14") (pinfunction "PF7(ADC7/TDI)_14") (pintype "bidirectional"))
      (node (ref "JP2") (pin "8") (pinfunction "8_8") (pintype "passive"))
    )
    (net (code "114") (name "SS") (class "Default")
      (node (ref "IC1") (pin "80") (pinfunction "(SS/PCINT0)PB0_80") (pintype "bidirectional"))
      (node (ref "U$1") (pin "23") (pinfunction "(SS)PB0_23") (pintype "bidirectional"))
      (node (ref "X13") (pin "5") (pinfunction "S_5") (pintype "passive"))
    )
    (net (code "115") (name "TXD0") (class "Default")
      (node (ref "IC1") (pin "32") (pinfunction "(TXD0)PE1_32") (pintype "bidirectional"))
      (node (ref "U$1") (pin "14") (pinfunction "(TXD0)PE1_14") (pintype "bidirectional"))
    )
    (net (code "116") (name "TXD1") (class "Default")
      (node (ref "IC1") (pin "26") (pinfunction "(TXD1/INT3)PD3_26") (pintype "bidirectional"))
      (node (ref "X1") (pin "2") (pinfunction "S_2") (pintype "passive"))
    )
    (net (code "117") (name "TXD2") (class "Default")
      (node (ref "IC1") (pin "28") (pinfunction "PH1(TXD2)_28") (pintype "bidirectional"))
      (node (ref "X2") (pin "2") (pinfunction "S_2") (pintype "passive"))
    )
    (net (code "118") (name "TXD3") (class "Default")
      (node (ref "IC1") (pin "30") (pinfunction "PJ1(TXD3/PCINT10)_30") (pintype "bidirectional"))
      (node (ref "X3") (pin "2") (pinfunction "S_2") (pintype "passive"))
    )
    (net (code "119") (name "VCC") (class "Default")
      (node (ref "IC1") (pin "6") (pinfunction "+VIN_6") (pintype "power_in"))
      (node (ref "U$1") (pin "6") (pinfunction "+VIN_6") (pintype "bidirectional"))
    )
    (net (code "120") (name "unconnected-(U$10-Pad4)") (class "Default")
      (node (ref "U$10") (pin "4") (pinfunction "4_4") (pintype "passive"))
    )
    (net (code "121") (name "~{RESET}") (class "Default")
      (node (ref "IC1") (pin "1") (pinfunction "~{RESET}_1") (pintype "bidirectional"))
      (node (ref "U$1") (pin "1") (pinfunction "~{RESET}_1") (pintype "bidirectional"))
    )
  )
)
